# driver_04_2_2018.net
KiCad netlist of a schematic drawn in EAGLE
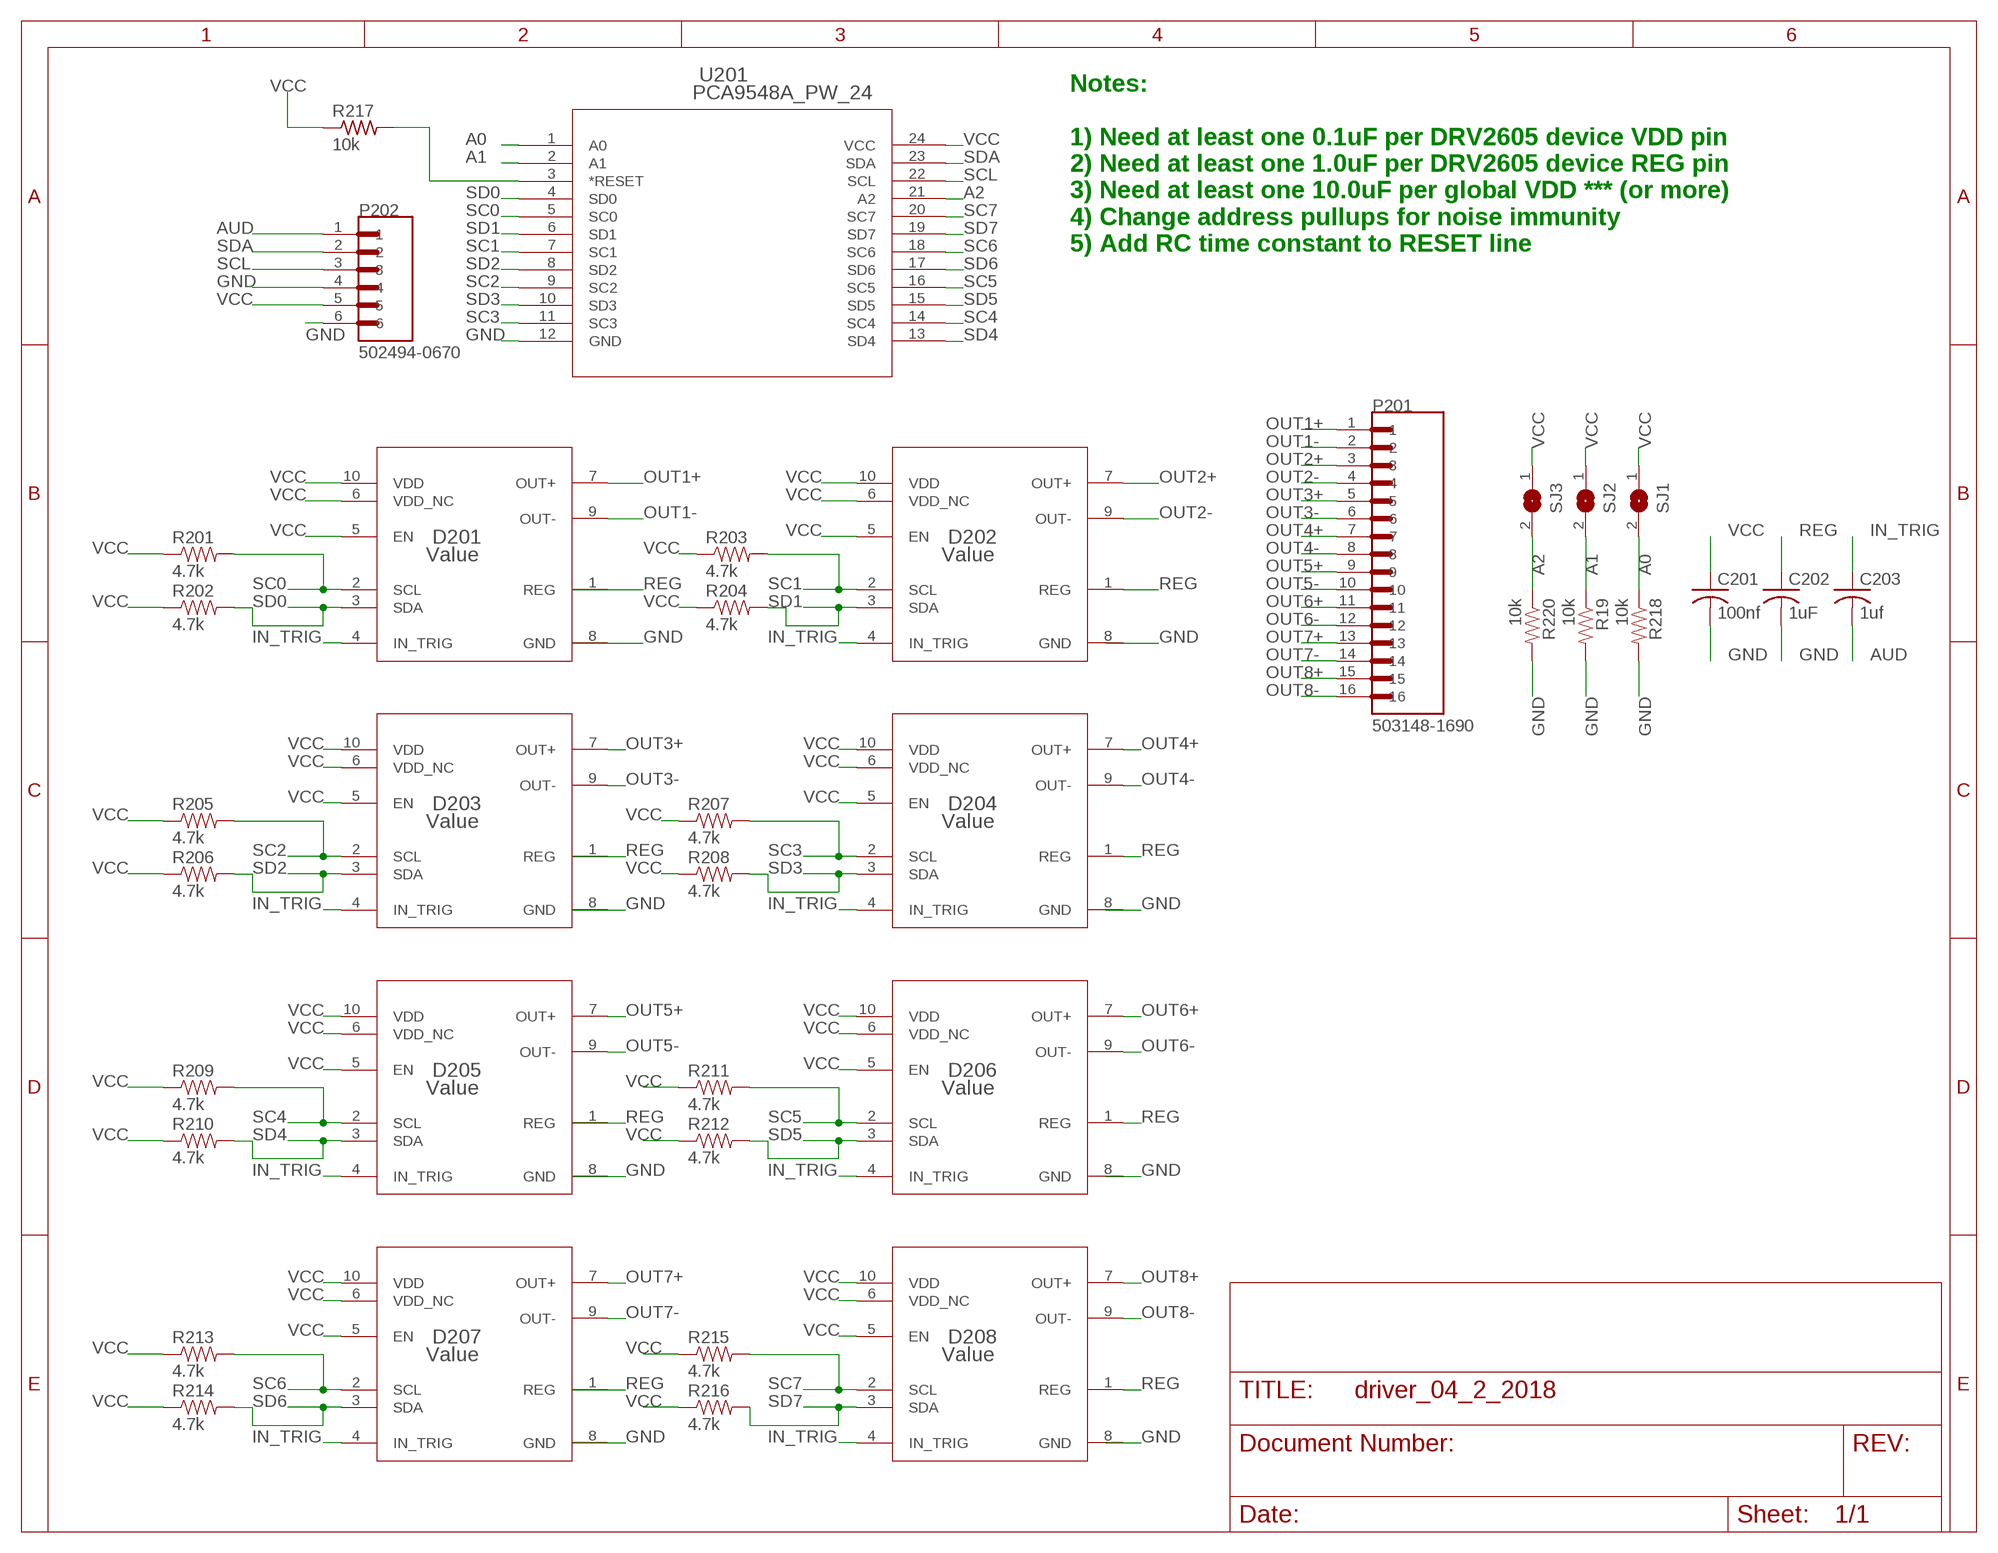
[diagram p0: schematic, sheet 1]

(export (version "E")
  (design (tool "Eeschema 10.0.6"))
  (components
    (comp (ref "C201")
      (value "100nf")
      (footprint "eagle-import:C0603")
      (libsource (lib "eagle-import") (part "C-USC0603"))
    )
    (comp (ref "C202")
      (value "1uF")
      (footprint "eagle-import:C0603")
      (libsource (lib "eagle-import") (part "C-USC0603"))
    )
    (comp (ref "C203")
      (value "1uf")
      (footprint "eagle-import:C0603")
      (libsource (lib "eagle-import") (part "C-USC0603"))
    )
    (comp (ref "D201")
      (value "Value")
      (footprint "eagle-import:DGS0010A")
      (fields (field (name "MANUFACTURER") "Texas Instruments") (field (name "PARTNUMBER") "DRV2605LDGS"))
      (libsource (lib "eagle-import") (part "DRV2605LDGSR"))
    )
    (comp (ref "D202")
      (value "Value")
      (footprint "eagle-import:DGS0010A")
      (fields (field (name "MANUFACTURER") "Texas Instruments") (field (name "PARTNUMBER") "DRV2605LDGS"))
      (libsource (lib "eagle-import") (part "DRV2605LDGSR"))
    )
    (comp (ref "D203")
      (value "Value")
      (footprint "eagle-import:DGS0010A")
      (fields (field (name "MANUFACTURER") "Texas Instruments") (field (name "PARTNUMBER") "DRV2605LDGS"))
      (libsource (lib "eagle-import") (part "DRV2605LDGSR"))
    )
    (comp (ref "D204")
      (value "Value")
      (footprint "eagle-import:DGS0010A")
      (fields (field (name "MANUFACTURER") "Texas Instruments") (field (name "PARTNUMBER") "DRV2605LDGS"))
      (libsource (lib "eagle-import") (part "DRV2605LDGSR"))
    )
    (comp (ref "D205")
      (value "Value")
      (footprint "eagle-import:DGS0010A")
      (fields (field (name "MANUFACTURER") "Texas Instruments") (field (name "PARTNUMBER") "DRV2605LDGS"))
      (libsource (lib "eagle-import") (part "DRV2605LDGSR"))
    )
    (comp (ref "D206")
      (value "Value")
      (footprint "eagle-import:DGS0010A")
      (fields (field (name "MANUFACTURER") "Texas Instruments") (field (name "PARTNUMBER") "DRV2605LDGS"))
      (libsource (lib "eagle-import") (part "DRV2605LDGSR"))
    )
    (comp (ref "D207")
      (value "Value")
      (footprint "eagle-import:DGS0010A")
      (fields (field (name "MANUFACTURER") "Texas Instruments") (field (name "PARTNUMBER") "DRV2605LDGS"))
      (libsource (lib "eagle-import") (part "DRV2605LDGSR"))
    )
    (comp (ref "D208")
      (value "Value")
      (footprint "eagle-import:DGS0010A")
      (fields (field (name "MANUFACTURER") "Texas Instruments") (field (name "PARTNUMBER") "DRV2605LDGS"))
      (libsource (lib "eagle-import") (part "DRV2605LDGSR"))
    )
    (comp (ref "P201")
      (value "503148-1690")
      (footprint "eagle-import:MOLEX_503148-1690")
      (fields (field (name "MF") "Molex"))
      (libsource (lib "eagle-import") (part "503148-1690"))
    )
    (comp (ref "P202")
      (value "502494-0670")
      (footprint "eagle-import:MOLEX_502494-0670")
      (fields (field (name "MF") "Molex"))
      (libsource (lib "eagle-import") (part "502494-0670"))
    )
    (comp (ref "R19")
      (value "10k")
      (footprint "eagle-import:EIA-0402")
      (libsource (lib "eagle-import") (part "RESISTOR0402-TYP"))
    )
    (comp (ref "R201")
      (value "4.7k")
      (footprint "eagle-import:EIA-0402")
      (libsource (lib "eagle-import") (part "RESISTOR0402-TYP"))
    )
    (comp (ref "R202")
      (value "4.7k")
      (footprint "eagle-import:EIA-0402")
      (libsource (lib "eagle-import") (part "RESISTOR0402-TYP"))
    )
    (comp (ref "R203")
      (value "4.7k")
      (footprint "eagle-import:EIA-0402")
      (libsource (lib "eagle-import") (part "RESISTOR0402-TYP"))
    )
    (comp (ref "R204")
      (value "4.7k")
      (footprint "eagle-import:EIA-0402")
      (libsource (lib "eagle-import") (part "RESISTOR0402-TYP"))
    )
    (comp (ref "R205")
      (value "4.7k")
      (footprint "eagle-import:EIA-0402")
      (libsource (lib "eagle-import") (part "RESISTOR0402-TYP"))
    )
    (comp (ref "R206")
      (value "4.7k")
      (footprint "eagle-import:EIA-0402")
      (libsource (lib "eagle-import") (part "RESISTOR0402-TYP"))
    )
    (comp (ref "R207")
      (value "4.7k")
      (footprint "eagle-import:EIA-0402")
      (libsource (lib "eagle-import") (part "RESISTOR0402-TYP"))
    )
    (comp (ref "R208")
      (value "4.7k")
      (footprint "eagle-import:EIA-0402")
      (libsource (lib "eagle-import") (part "RESISTOR0402-TYP"))
    )
    (comp (ref "R209")
      (value "4.7k")
      (footprint "eagle-import:EIA-0402")
      (libsource (lib "eagle-import") (part "RESISTOR0402-TYP"))
    )
    (comp (ref "R210")
      (value "4.7k")
      (footprint "eagle-import:EIA-0402")
      (libsource (lib "eagle-import") (part "RESISTOR0402-TYP"))
    )
    (comp (ref "R211")
      (value "4.7k")
      (footprint "eagle-import:EIA-0402")
      (libsource (lib "eagle-import") (part "RESISTOR0402-TYP"))
    )
    (comp (ref "R212")
      (value "4.7k")
      (footprint "eagle-import:EIA-0402")
      (libsource (lib "eagle-import") (part "RESISTOR0402-TYP"))
    )
    (comp (ref "R213")
      (value "4.7k")
      (footprint "eagle-import:EIA-0402")
      (libsource (lib "eagle-import") (part "RESISTOR0402-TYP"))
    )
    (comp (ref "R214")
      (value "4.7k")
      (footprint "eagle-import:EIA-0402")
      (libsource (lib "eagle-import") (part "RESISTOR0402-TYP"))
    )
    (comp (ref "R215")
      (value "4.7k")
      (footprint "eagle-import:EIA-0402")
      (libsource (lib "eagle-import") (part "RESISTOR0402-TYP"))
    )
    (comp (ref "R216")
      (value "4.7k")
      (footprint "eagle-import:EIA-0402")
      (libsource (lib "eagle-import") (part "RESISTOR0402-TYP"))
    )
    (comp (ref "R217")
      (value "10k")
      (footprint "eagle-import:R0402")
      (libsource (lib "eagle-import") (part "R-US_R0402"))
    )
    (comp (ref "R218")
      (value "10k")
      (footprint "eagle-import:EIA-0402")
      (libsource (lib "eagle-import") (part "RESISTOR0402-TYP"))
    )
    (comp (ref "R220")
      (value "10k")
      (footprint "eagle-import:EIA-0402")
      (libsource (lib "eagle-import") (part "RESISTOR0402-TYP"))
    )
    (comp (ref "SJ1") (value "SJ") (footprint "eagle-import:SJ") (libsource (lib "eagle-import") (part "SJ")))
    (comp (ref "SJ2") (value "SJ") (footprint "eagle-import:SJ") (libsource (lib "eagle-import") (part "SJ")))
    (comp (ref "SJ3") (value "SJ") (footprint "eagle-import:SJ") (libsource (lib "eagle-import") (part "SJ")))
    (comp (ref "U201")
      (value "PCA9548A_PW_24")
      (footprint "eagle-import:PW24")
      (fields
        (field (name "GENERIC_PART_NUMBER") "PCA9548A")
        (field (name "MANUFACTURER") "Texas Instruments")
        (field (name "MANUFACTURER_PART_NUMBER") "pca9548a_pw_24")
      )
      (libsource (lib "eagle-import") (part "PCA9548A_PW_24"))
    )
  )
  (nets
    (net (code "1") (name "/A0") (class "Default")
      (node (ref "R218") (pin "1") (pinfunction "1_1") (pintype "passive"))
      (node (ref "SJ1") (pin "2") (pinfunction "2_2") (pintype "passive"))
      (node (ref "U201") (pin "1") (pinfunction "A0_1") (pintype "input"))
    )
    (net (code "2") (name "/A1") (class "Default")
      (node (ref "R19") (pin "1") (pinfunction "1_1") (pintype "passive"))
      (node (ref "SJ2") (pin "2") (pinfunction "2_2") (pintype "passive"))
      (node (ref "U201") (pin "2") (pinfunction "A1_2") (pintype "input"))
    )
    (net (code "3") (name "/A2") (class "Default")
      (node (ref "R220") (pin "1") (pinfunction "1_1") (pintype "passive"))
      (node (ref "SJ3") (pin "2") (pinfunction "2_2") (pintype "passive"))
      (node (ref "U201") (pin "21") (pinfunction "A2_21") (pintype "input"))
    )
    (net (code "4") (name "/AUD") (class "Default")
      (node (ref "C203") (pin "2") (pinfunction "2_2") (pintype "passive"))
      (node (ref "P202") (pin "1") (pinfunction "1_1") (pintype "passive"))
    )
    (net (code "5") (name "/GND") (class "Default")
      (node (ref "C201") (pin "2") (pinfunction "2_2") (pintype "passive"))
      (node (ref "C202") (pin "2") (pinfunction "2_2") (pintype "passive"))
      (node (ref "D201") (pin "8") (pinfunction "GND_8") (pintype "power_in"))
      (node (ref "D202") (pin "8") (pinfunction "GND_8") (pintype "power_in"))
      (node (ref "D203") (pin "8") (pinfunction "GND_8") (pintype "power_in"))
      (node (ref "D204") (pin "8") (pinfunction "GND_8") (pintype "power_in"))
      (node (ref "D205") (pin "8") (pinfunction "GND_8") (pintype "power_in"))
      (node (ref "D206") (pin "8") (pinfunction "GND_8") (pintype "power_in"))
      (node (ref "D207") (pin "8") (pinfunction "GND_8") (pintype "power_in"))
      (node (ref "D208") (pin "8") (pinfunction "GND_8") (pintype "power_in"))
      (node (ref "P202") (pin "4") (pinfunction "4_4") (pintype "passive"))
      (node (ref "P202") (pin "6") (pinfunction "6_6") (pintype "passive"))
      (node (ref "R19") (pin "2") (pinfunction "2_2") (pintype "passive"))
      (node (ref "R218") (pin "2") (pinfunction "2_2") (pintype "passive"))
      (node (ref "R220") (pin "2") (pinfunction "2_2") (pintype "passive"))
      (node (ref "U201") (pin "12") (pinfunction "GND_12") (pintype "power_in"))
    )
    (net (code "6") (name "/IN_TRIG") (class "Default")
      (node (ref "C203") (pin "1") (pinfunction "1_1") (pintype "passive"))
      (node (ref "D201") (pin "4") (pinfunction "IN_TRIG_4") (pintype "input"))
      (node (ref "D202") (pin "4") (pinfunction "IN_TRIG_4") (pintype "input"))
      (node (ref "D203") (pin "4") (pinfunction "IN_TRIG_4") (pintype "input"))
      (node (ref "D204") (pin "4") (pinfunction "IN_TRIG_4") (pintype "input"))
      (node (ref "D205") (pin "4") (pinfunction "IN_TRIG_4") (pintype "input"))
      (node (ref "D206") (pin "4") (pinfunction "IN_TRIG_4") (pintype "input"))
      (node (ref "D207") (pin "4") (pinfunction "IN_TRIG_4") (pintype "input"))
      (node (ref "D208") (pin "4") (pinfunction "IN_TRIG_4") (pintype "input"))
    )
    (net (code "7") (name "/OUT1+") (class "Default")
      (node (ref "D201") (pin "7") (pinfunction "OUT+_7") (pintype "output"))
      (node (ref "P201") (pin "1") (pinfunction "1_1") (pintype "passive"))
    )
    (net (code "8") (name "/OUT1-") (class "Default")
      (node (ref "D201") (pin "9") (pinfunction "OUT-_9") (pintype "output"))
      (node (ref "P201") (pin "2") (pinfunction "2_2") (pintype "passive"))
    )
    (net (code "9") (name "/OUT2+") (class "Default")
      (node (ref "D202") (pin "7") (pinfunction "OUT+_7") (pintype "output"))
      (node (ref "P201") (pin "3") (pinfunction "3_3") (pintype "passive"))
    )
    (net (code "10") (name "/OUT2-") (class "Default")
      (node (ref "D202") (pin "9") (pinfunction "OUT-_9") (pintype "output"))
      (node (ref "P201") (pin "4") (pinfunction "4_4") (pintype "passive"))
    )
    (net (code "11") (name "/OUT3+") (class "Default")
      (node (ref "D203") (pin "7") (pinfunction "OUT+_7") (pintype "output"))
      (node (ref "P201") (pin "5") (pinfunction "5_5") (pintype "passive"))
    )
    (net (code "12") (name "/OUT3-") (class "Default")
      (node (ref "D203") (pin "9") (pinfunction "OUT-_9") (pintype "output"))
      (node (ref "P201") (pin "6") (pinfunction "6_6") (pintype "passive"))
    )
    (net (code "13") (name "/OUT4+") (class "Default")
      (node (ref "D204") (pin "7") (pinfunction "OUT+_7") (pintype "output"))
      (node (ref "P201") (pin "7") (pinfunction "7_7") (pintype "passive"))
    )
    (net (code "14") (name "/OUT4-") (class "Default")
      (node (ref "D204") (pin "9") (pinfunction "OUT-_9") (pintype "output"))
      (node (ref "P201") (pin "8") (pinfunction "8_8") (pintype "passive"))
    )
    (net (code "15") (name "/OUT5+") (class "Default")
      (node (ref "D205") (pin "7") (pinfunction "OUT+_7") (pintype "output"))
      (node (ref "P201") (pin "9") (pinfunction "9_9") (pintype "passive"))
    )
    (net (code "16") (name "/OUT5-") (class "Default")
      (node (ref "D205") (pin "9") (pinfunction "OUT-_9") (pintype "output"))
      (node (ref "P201") (pin "10") (pinfunction "10_10") (pintype "passive"))
    )
    (net (code "17") (name "/OUT6+") (class "Default")
      (node (ref "D206") (pin "7") (pinfunction "OUT+_7") (pintype "output"))
      (node (ref "P201") (pin "11") (pinfunction "11_11") (pintype "passive"))
    )
    (net (code "18") (name "/OUT6-") (class "Default")
      (node (ref "D206") (pin "9") (pinfunction "OUT-_9") (pintype "output"))
      (node (ref "P201") (pin "12") (pinfunction "12_12") (pintype "passive"))
    )
    (net (code "19") (name "/OUT7+") (class "Default")
      (node (ref "D207") (pin "7") (pinfunction "OUT+_7") (pintype "output"))
      (node (ref "P201") (pin "13") (pinfunction "13_13") (pintype "passive"))
    )
    (net (code "20") (name "/OUT7-") (class "Default")
      (node (ref "D207") (pin "9") (pinfunction "OUT-_9") (pintype "output"))
      (node (ref "P201") (pin "14") (pinfunction "14_14") (pintype "passive"))
    )
    (net (code "21") (name "/OUT8+") (class "Default")
      (node (ref "D208") (pin "7") (pinfunction "OUT+_7") (pintype "output"))
      (node (ref "P201") (pin "15") (pinfunction "15_15") (pintype "passive"))
    )
    (net (code "22") (name "/OUT8-") (class "Default")
      (node (ref "D208") (pin "9") (pinfunction "OUT-_9") (pintype "output"))
      (node (ref "P201") (pin "16") (pinfunction "16_16") (pintype "passive"))
    )
    (net (code "23") (name "/REG") (class "Default")
      (node (ref "C202") (pin "1") (pinfunction "1_1") (pintype "passive"))
      (node (ref "D201") (pin "1") (pinfunction "REG_1") (pintype "power_in"))
      (node (ref "D202") (pin "1") (pinfunction "REG_1") (pintype "power_in"))
      (node (ref "D203") (pin "1") (pinfunction "REG_1") (pintype "power_in"))
      (node (ref "D204") (pin "1") (pinfunction "REG_1") (pintype "power_in"))
      (node (ref "D205") (pin "1") (pinfunction "REG_1") (pintype "power_in"))
      (node (ref "D206") (pin "1") (pinfunction "REG_1") (pintype "power_in"))
      (node (ref "D207") (pin "1") (pinfunction "REG_1") (pintype "power_in"))
      (node (ref "D208") (pin "1") (pinfunction "REG_1") (pintype "power_in"))
    )
    (net (code "24") (name "/SC0") (class "Default")
      (node (ref "D201") (pin "2") (pinfunction "SCL_2") (pintype "input"))
      (node (ref "R201") (pin "2") (pinfunction "2_2") (pintype "passive"))
      (node (ref "U201") (pin "5") (pinfunction "SC0_5") (pintype "passive"))
    )
    (net (code "25") (name "/SC1") (class "Default")
      (node (ref "D202") (pin "2") (pinfunction "SCL_2") (pintype "input"))
      (node (ref "R203") (pin "2") (pinfunction "2_2") (pintype "passive"))
      (node (ref "U201") (pin "7") (pinfunction "SC1_7") (pintype "passive"))
    )
    (net (code "26") (name "/SC2") (class "Default")
      (node (ref "D203") (pin "2") (pinfunction "SCL_2") (pintype "input"))
      (node (ref "R205") (pin "2") (pinfunction "2_2") (pintype "passive"))
      (node (ref "U201") (pin "9") (pinfunction "SC2_9") (pintype "passive"))
    )
    (net (code "27") (name "/SC3") (class "Default")
      (node (ref "D204") (pin "2") (pinfunction "SCL_2") (pintype "input"))
      (node (ref "R207") (pin "2") (pinfunction "2_2") (pintype "passive"))
      (node (ref "U201") (pin "11") (pinfunction "SC3_11") (pintype "passive"))
    )
    (net (code "28") (name "/SC4") (class "Default")
      (node (ref "D205") (pin "2") (pinfunction "SCL_2") (pintype "input"))
      (node (ref "R209") (pin "2") (pinfunction "2_2") (pintype "passive"))
      (node (ref "U201") (pin "14") (pinfunction "SC4_14") (pintype "passive"))
    )
    (net (code "29") (name "/SC5") (class "Default")
      (node (ref "D206") (pin "2") (pinfunction "SCL_2") (pintype "input"))
      (node (ref "R211") (pin "2") (pinfunction "2_2") (pintype "passive"))
      (node (ref "U201") (pin "16") (pinfunction "SC5_16") (pintype "passive"))
    )
    (net (code "30") (name "/SC6") (class "Default")
      (node (ref "D207") (pin "2") (pinfunction "SCL_2") (pintype "input"))
      (node (ref "R213") (pin "2") (pinfunction "2_2") (pintype "passive"))
      (node (ref "U201") (pin "18") (pinfunction "SC6_18") (pintype "passive"))
    )
    (net (code "31") (name "/SC7") (class "Default")
      (node (ref "D208") (pin "2") (pinfunction "SCL_2") (pintype "input"))
      (node (ref "R215") (pin "2") (pinfunction "2_2") (pintype "passive"))
      (node (ref "U201") (pin "20") (pinfunction "SC7_20") (pintype "passive"))
    )
    (net (code "32") (name "/SCL") (class "Default")
      (node (ref "P202") (pin "3") (pinfunction "3_3") (pintype "passive"))
      (node (ref "U201") (pin "22") (pinfunction "SCL_22") (pintype "passive"))
    )
    (net (code "33") (name "/SD0") (class "Default")
      (node (ref "D201") (pin "3") (pinfunction "SDA_3") (pintype "bidirectional"))
      (node (ref "R202") (pin "2") (pinfunction "2_2") (pintype "passive"))
      (node (ref "U201") (pin "4") (pinfunction "SD0_4") (pintype "passive"))
    )
    (net (code "34") (name "/SD1") (class "Default")
      (node (ref "D202") (pin "3") (pinfunction "SDA_3") (pintype "bidirectional"))
      (node (ref "R204") (pin "2") (pinfunction "2_2") (pintype "passive"))
      (node (ref "U201") (pin "6") (pinfunction "SD1_6") (pintype "passive"))
    )
    (net (code "35") (name "/SD2") (class "Default")
      (node (ref "D203") (pin "3") (pinfunction "SDA_3") (pintype "bidirectional"))
      (node (ref "R206") (pin "2") (pinfunction "2_2") (pintype "passive"))
      (node (ref "U201") (pin "8") (pinfunction "SD2_8") (pintype "passive"))
    )
    (net (code "36") (name "/SD3") (class "Default")
      (node (ref "D204") (pin "3") (pinfunction "SDA_3") (pintype "bidirectional"))
      (node (ref "R208") (pin "2") (pinfunction "2_2") (pintype "passive"))
      (node (ref "U201") (pin "10") (pinfunction "SD3_10") (pintype "passive"))
    )
    (net (code "37") (name "/SD4") (class "Default")
      (node (ref "D205") (pin "3") (pinfunction "SDA_3") (pintype "bidirectional"))
      (node (ref "R210") (pin "2") (pinfunction "2_2") (pintype "passive"))
      (node (ref "U201") (pin "13") (pinfunction "SD4_13") (pintype "passive"))
    )
    (net (code "38") (name "/SD5") (class "Default")
      (node (ref "D206") (pin "3") (pinfunction "SDA_3") (pintype "bidirectional"))
      (node (ref "R212") (pin "2") (pinfunction "2_2") (pintype "passive"))
      (node (ref "U201") (pin "15") (pinfunction "SD5_15") (pintype "passive"))
    )
    (net (code "39") (name "/SD6") (class "Default")
      (node (ref "D207") (pin "3") (pinfunction "SDA_3") (pintype "bidirectional"))
      (node (ref "R214") (pin "2") (pinfunction "2_2") (pintype "passive"))
      (node (ref "U201") (pin "17") (pinfunction "SD6_17") (pintype "passive"))
    )
    (net (code "40") (name "/SD7") (class "Default")
      (node (ref "D208") (pin "3") (pinfunction "SDA_3") (pintype "bidirectional"))
      (node (ref "R216") (pin "2") (pinfunction "2_2") (pintype "passive"))
      (node (ref "U201") (pin "19") (pinfunction "SD7_19") (pintype "passive"))
    )
    (net (code "41") (name "/SDA") (class "Default")
      (node (ref "P202") (pin "2") (pinfunction "2_2") (pintype "passive"))
      (node (ref "U201") (pin "23") (pinfunction "SDA_23") (pintype "passive"))
    )
    (net (code "42") (name "/VCC") (class "Default")
      (node (ref "C201") (pin "1") (pinfunction "1_1") (pintype "passive"))
      (node (ref "D201") (pin "10") (pinfunction "VDD_10") (pintype "power_in"))
      (node (ref "D201") (pin "5") (pinfunction "EN_5") (pintype "input"))
      (node (ref "D201") (pin "6") (pinfunction "VDD_NC_6") (pintype "power_in"))
      (node (ref "D202") (pin "10") (pinfunction "VDD_10") (pintype "power_in"))
      (node (ref "D202") (pin "5") (pinfunction "EN_5") (pintype "input"))
      (node (ref "D202") (pin "6") (pinfunction "VDD_NC_6") (pintype "power_in"))
      (node (ref "D203") (pin "10") (pinfunction "VDD_10") (pintype "power_in"))
      (node (ref "D203") (pin "5") (pinfunction "EN_5") (pintype "input"))
      (node (ref "D203") (pin "6") (pinfunction "VDD_NC_6") (pintype "power_in"))
      (node (ref "D204") (pin "10") (pinfunction "VDD_10") (pintype "power_in"))
      (node (ref "D204") (pin "5") (pinfunction "EN_5") (pintype "input"))
      (node (ref "D204") (pin "6") (pinfunction "VDD_NC_6") (pintype "power_in"))
      (node (ref "D205") (pin "10") (pinfunction "VDD_10") (pintype "power_in"))
      (node (ref "D205") (pin "5") (pinfunction "EN_5") (pintype "input"))
      (node (ref "D205") (pin "6") (pinfunction "VDD_NC_6") (pintype "power_in"))
      (node (ref "D206") (pin "10") (pinfunction "VDD_10") (pintype "power_in"))
      (node (ref "D206") (pin "5") (pinfunction "EN_5") (pintype "input"))
      (node (ref "D206") (pin "6") (pinfunction "VDD_NC_6") (pintype "power_in"))
      (node (ref "D207") (pin "10") (pinfunction "VDD_10") (pintype "power_in"))
      (node (ref "D207") (pin "5") (pinfunction "EN_5") (pintype "input"))
      (node (ref "D207") (pin "6") (pinfunction "VDD_NC_6") (pintype "power_in"))
      (node (ref "D208") (pin "10") (pinfunction "VDD_10") (pintype "power_in"))
      (node (ref "D208") (pin "5") (pinfunction "EN_5") (pintype "input"))
      (node (ref "D208") (pin "6") (pinfunction "VDD_NC_6") (pintype "power_in"))
      (node (ref "P202") (pin "5") (pinfunction "5_5") (pintype "passive"))
      (node (ref "R201") (pin "1") (pinfunction "1_1") (pintype "passive"))
      (node (ref "R202") (pin "1") (pinfunction "1_1") (pintype "passive"))
      (node (ref "R203") (pin "1") (pinfunction "1_1") (pintype "passive"))
      (node (ref "R204") (pin "1") (pinfunction "1_1") (pintype "passive"))
      (node (ref "R205") (pin "1") (pinfunction "1_1") (pintype "passive"))
      (node (ref "R206") (pin "1") (pinfunction "1_1") (pintype "passive"))
      (node (ref "R207") (pin "1") (pinfunction "1_1") (pintype "passive"))
      (node (ref "R208") (pin "1") (pinfunction "1_1") (pintype "passive"))
      (node (ref "R209") (pin "1") (pinfunction "1_1") (pintype "passive"))
      (node (ref "R210") (pin "1") (pinfunction "1_1") (pintype "passive"))
      (node (ref "R211") (pin "1") (pinfunction "1_1") (pintype "passive"))
      (node (ref "R212") (pin "1") (pinfunction "1_1") (pintype "passive"))
      (node (ref "R213") (pin "1") (pinfunction "1_1") (pintype "passive"))
      (node (ref "R214") (pin "1") (pinfunction "1_1") (pintype "passive"))
      (node (ref "R215") (pin "1") (pinfunction "1_1") (pintype "passive"))
      (node (ref "R216") (pin "1") (pinfunction "1_1") (pintype "passive"))
      (node (ref "R217") (pin "1") (pinfunction "1_1") (pintype "passive"))
      (node (ref "SJ1") (pin "1") (pinfunction "1_1") (pintype "passive"))
      (node (ref "SJ2") (pin "1") (pinfunction "1_1") (pintype "passive"))
      (node (ref "SJ3") (pin "1") (pinfunction "1_1") (pintype "passive"))
      (node (ref "U201") (pin "24") (pinfunction "VCC_24") (pintype "power_in"))
    )
    (net (code "43") (name "Net-(U201-*RESET)") (class "Default")
      (node (ref "R217") (pin "2") (pinfunction "2_2") (pintype "passive"))
      (node (ref "U201") (pin "3") (pinfunction "*RESET_3") (pintype "input"))
    )
  )
)
